# Focuser-proto.net
KiCad netlist of a schematic drawn in EAGLE
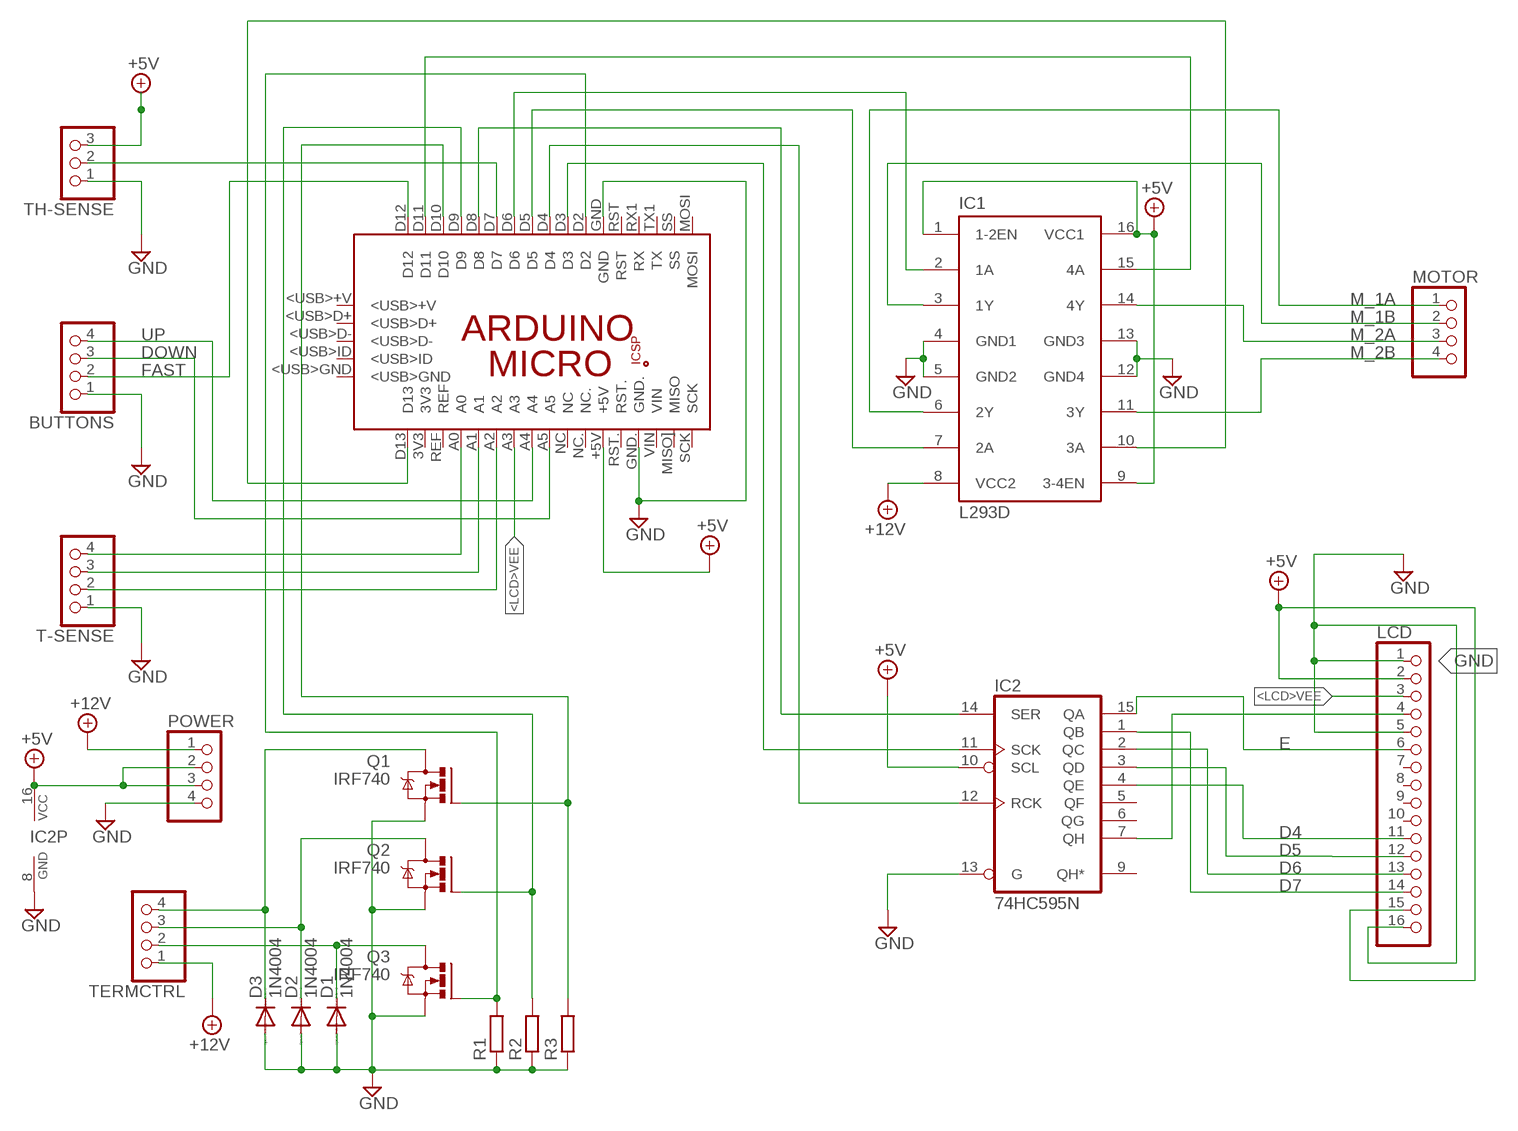
[diagram p0: schematic, sheet 1]

(export (version "E")
  (design (tool "Eeschema 10.0.6"))
  (components
    (comp (ref "BUTTONS")
      (value "PINHD-1X4")
      (footprint "eagle-import:1X04")
      (libsource (lib "eagle-import") (part "PINHD-1X4"))
    )
    (comp (ref "D1")
      (value "1N4004")
      (footprint "eagle-import:DO41-10")
      (libsource (lib "eagle-import") (part "1N4004"))
    )
    (comp (ref "D2")
      (value "1N4004")
      (footprint "eagle-import:DO41-10")
      (libsource (lib "eagle-import") (part "1N4004"))
    )
    (comp (ref "D3")
      (value "1N4004")
      (footprint "eagle-import:DO41-10")
      (libsource (lib "eagle-import") (part "1N4004"))
    )
    (comp (ref "IC1")
      (value "L293D")
      (footprint "eagle-import:DIL16")
      (libsource (lib "eagle-import") (part "L293D"))
    )
    (comp (ref "IC2")
      (value "74HC595N")
      (footprint "eagle-import:DIL16")
      (libsource (lib "eagle-import") (part "74595NHC"))
    )
    (comp (ref "LCD")
      (value "PINHD-1X16")
      (footprint "eagle-import:1X16")
      (libsource (lib "eagle-import") (part "PINHD-1X16"))
    )
    (comp (ref "MOTOR")
      (value "PINHD-1X4")
      (footprint "eagle-import:1X04")
      (libsource (lib "eagle-import") (part "PINHD-1X4"))
    )
    (comp (ref "PCB1")
      (value "ARDUINO_MICRO")
      (footprint "eagle-import:ARDUINO_MICRO")
      (libsource (lib "eagle-import") (part "ARDUINO_MICRO"))
    )
    (comp (ref "POWER")
      (value "PINHD-1X4")
      (footprint "eagle-import:1X04")
      (libsource (lib "eagle-import") (part "PINHD-1X4"))
    )
    (comp (ref "Q1")
      (value "IRF740")
      (footprint "eagle-import:TO220BV")
      (libsource (lib "eagle-import") (part "IRF740"))
    )
    (comp (ref "Q2")
      (value "IRF740")
      (footprint "eagle-import:TO220BV")
      (libsource (lib "eagle-import") (part "IRF740"))
    )
    (comp (ref "Q3")
      (value "IRF740")
      (footprint "eagle-import:TO220BV")
      (libsource (lib "eagle-import") (part "IRF740"))
    )
    (comp (ref "R1")
      (value "R-EU_0207/7")
      (footprint "eagle-import:0207_7")
      (libsource (lib "eagle-import") (part "R-EU_0207/7"))
    )
    (comp (ref "R2")
      (value "R-EU_0207/7")
      (footprint "eagle-import:0207_7")
      (libsource (lib "eagle-import") (part "R-EU_0207/7"))
    )
    (comp (ref "R3")
      (value "R-EU_0207/7")
      (footprint "eagle-import:0207_7")
      (libsource (lib "eagle-import") (part "R-EU_0207/7"))
    )
    (comp (ref "T-SENSE")
      (value "PINHD-1X4")
      (footprint "eagle-import:1X04")
      (libsource (lib "eagle-import") (part "PINHD-1X4"))
    )
    (comp (ref "TERMCTRL")
      (value "PINHD-1X4")
      (footprint "eagle-import:1X04")
      (libsource (lib "eagle-import") (part "PINHD-1X4"))
    )
    (comp (ref "TH-SENSE")
      (value "PINHD-1X3")
      (footprint "eagle-import:1X03")
      (libsource (lib "eagle-import") (part "PINHD-1X3"))
    )
  )
  (nets
    (net (code "1") (name "+5V") (class "Default")
      (node (ref "IC1") (pin "1") (pinfunction "1-2EN_1") (pintype "input"))
      (node (ref "IC1") (pin "16") (pinfunction "VCC1_16") (pintype "power_in"))
      (node (ref "IC1") (pin "9") (pinfunction "3-4EN_9") (pintype "input"))
      (node (ref "IC2") (pin "10") (pinfunction "SCL_10") (pintype "input"))
      (node (ref "IC2") (pin "16") (pinfunction "VCC_16") (pintype "power_in"))
      (node (ref "LCD") (pin "15") (pinfunction "15_15") (pintype "passive"))
      (node (ref "LCD") (pin "2") (pinfunction "2_2") (pintype "passive"))
      (node (ref "PCB1") (pin "+5V") (pinfunction "+5V_+5V") (pintype "bidirectional"))
      (node (ref "POWER") (pin "2") (pinfunction "2_2") (pintype "passive"))
      (node (ref "POWER") (pin "3") (pinfunction "3_3") (pintype "passive"))
      (node (ref "TH-SENSE") (pin "3") (pinfunction "3_3") (pintype "passive"))
    )
    (net (code "2") (name "+12V") (class "Default")
      (node (ref "IC1") (pin "8") (pinfunction "VCC2_8") (pintype "power_in"))
      (node (ref "POWER") (pin "1") (pinfunction "1_1") (pintype "passive"))
      (node (ref "TERMCTRL") (pin "1") (pinfunction "1_1") (pintype "passive"))
    )
    (net (code "3") (name "/D4") (class "Default")
      (node (ref "IC2") (pin "4") (pinfunction "QE_4") (pintype "tri_state"))
      (node (ref "LCD") (pin "11") (pinfunction "11_11") (pintype "passive"))
    )
    (net (code "4") (name "/D5") (class "Default")
      (node (ref "IC2") (pin "3") (pinfunction "QD_3") (pintype "tri_state"))
      (node (ref "LCD") (pin "12") (pinfunction "12_12") (pintype "passive"))
    )
    (net (code "5") (name "/D6") (class "Default")
      (node (ref "IC2") (pin "2") (pinfunction "QC_2") (pintype "tri_state"))
      (node (ref "LCD") (pin "13") (pinfunction "13_13") (pintype "passive"))
    )
    (net (code "6") (name "/D7") (class "Default")
      (node (ref "IC2") (pin "1") (pinfunction "QB_1") (pintype "tri_state"))
      (node (ref "LCD") (pin "14") (pinfunction "14_14") (pintype "passive"))
    )
    (net (code "7") (name "/DOWN") (class "Default")
      (node (ref "BUTTONS") (pin "3") (pinfunction "3_3") (pintype "passive"))
      (node (ref "PCB1") (pin "A5") (pinfunction "A5_A5") (pintype "bidirectional"))
    )
    (net (code "8") (name "/E") (class "Default")
      (node (ref "IC2") (pin "15") (pinfunction "QA_15") (pintype "tri_state"))
      (node (ref "LCD") (pin "6") (pinfunction "6_6") (pintype "passive"))
    )
    (net (code "9") (name "/FAST") (class "Default")
      (node (ref "BUTTONS") (pin "2") (pinfunction "2_2") (pintype "passive"))
      (node (ref "PCB1") (pin "D12") (pinfunction "D12_D12") (pintype "bidirectional"))
    )
    (net (code "10") (name "/M_1A") (class "Default")
      (node (ref "IC1") (pin "6") (pinfunction "2Y_6") (pintype "output"))
      (node (ref "MOTOR") (pin "1") (pinfunction "1_1") (pintype "passive"))
    )
    (net (code "11") (name "/M_1B") (class "Default")
      (node (ref "IC1") (pin "3") (pinfunction "1Y_3") (pintype "output"))
      (node (ref "MOTOR") (pin "2") (pinfunction "2_2") (pintype "passive"))
    )
    (net (code "12") (name "/M_2A") (class "Default")
      (node (ref "IC1") (pin "14") (pinfunction "4Y_14") (pintype "output"))
      (node (ref "MOTOR") (pin "3") (pinfunction "3_3") (pintype "passive"))
    )
    (net (code "13") (name "/M_2B") (class "Default")
      (node (ref "IC1") (pin "11") (pinfunction "3Y_11") (pintype "output"))
      (node (ref "MOTOR") (pin "4") (pinfunction "4_4") (pintype "passive"))
    )
    (net (code "14") (name "/UP") (class "Default")
      (node (ref "BUTTONS") (pin "4") (pinfunction "4_4") (pintype "passive"))
      (node (ref "PCB1") (pin "A4") (pinfunction "A4_A4") (pintype "bidirectional"))
    )
    (net (code "15") (name "<LCD>VEE") (class "Default")
      (node (ref "LCD") (pin "3") (pinfunction "3_3") (pintype "passive"))
      (node (ref "PCB1") (pin "A3") (pinfunction "A3_A3") (pintype "bidirectional"))
    )
    (net (code "16") (name "GND") (class "Default")
      (node (ref "BUTTONS") (pin "1") (pinfunction "1_1") (pintype "passive"))
      (node (ref "D1") (pin "A") (pinfunction "A_A") (pintype "passive"))
      (node (ref "D2") (pin "A") (pinfunction "A_A") (pintype "passive"))
      (node (ref "D3") (pin "A") (pinfunction "A_A") (pintype "passive"))
      (node (ref "IC1") (pin "12") (pinfunction "GND4_12") (pintype "power_in"))
      (node (ref "IC1") (pin "13") (pinfunction "GND3_13") (pintype "power_in"))
      (node (ref "IC1") (pin "4") (pinfunction "GND1_4") (pintype "power_in"))
      (node (ref "IC1") (pin "5") (pinfunction "GND2_5") (pintype "power_in"))
      (node (ref "IC2") (pin "13") (pinfunction "G_13") (pintype "input"))
      (node (ref "IC2") (pin "8") (pinfunction "GND_8") (pintype "power_in"))
      (node (ref "LCD") (pin "1") (pinfunction "1_1") (pintype "passive"))
      (node (ref "LCD") (pin "16") (pinfunction "16_16") (pintype "passive"))
      (node (ref "LCD") (pin "5") (pinfunction "5_5") (pintype "passive"))
      (node (ref "PCB1") (pin "GND") (pinfunction "GND_GND") (pintype "bidirectional"))
      (node (ref "PCB1") (pin "GND.") (pinfunction "GND._GND.") (pintype "bidirectional"))
      (node (ref "POWER") (pin "4") (pinfunction "4_4") (pintype "passive"))
      (node (ref "Q1") (pin "S") (pinfunction "S_S") (pintype "passive"))
      (node (ref "Q2") (pin "S") (pinfunction "S_S") (pintype "passive"))
      (node (ref "Q3") (pin "S") (pinfunction "S_S") (pintype "passive"))
      (node (ref "R1") (pin "1") (pinfunction "1_1") (pintype "passive"))
      (node (ref "R2") (pin "1") (pinfunction "1_1") (pintype "passive"))
      (node (ref "R3") (pin "1") (pinfunction "1_1") (pintype "passive"))
      (node (ref "T-SENSE") (pin "1") (pinfunction "1_1") (pintype "passive"))
      (node (ref "TH-SENSE") (pin "1") (pinfunction "1_1") (pintype "passive"))
    )
    (net (code "17") (name "Net-(D1-PadC)") (class "Default")
      (node (ref "D1") (pin "C") (pinfunction "C_C") (pintype "passive"))
      (node (ref "Q3") (pin "D") (pinfunction "D_D") (pintype "passive"))
      (node (ref "TERMCTRL") (pin "2") (pinfunction "2_2") (pintype "passive"))
    )
    (net (code "18") (name "Net-(D2-PadC)") (class "Default")
      (node (ref "D2") (pin "C") (pinfunction "C_C") (pintype "passive"))
      (node (ref "Q2") (pin "D") (pinfunction "D_D") (pintype "passive"))
      (node (ref "TERMCTRL") (pin "3") (pinfunction "3_3") (pintype "passive"))
    )
    (net (code "19") (name "Net-(D3-PadC)") (class "Default")
      (node (ref "D3") (pin "C") (pinfunction "C_C") (pintype "passive"))
      (node (ref "Q1") (pin "D") (pinfunction "D_D") (pintype "passive"))
      (node (ref "TERMCTRL") (pin "4") (pinfunction "4_4") (pintype "passive"))
    )
    (net (code "20") (name "Net-(IC1-1A)") (class "Default")
      (node (ref "IC1") (pin "2") (pinfunction "1A_2") (pintype "input"))
      (node (ref "PCB1") (pin "D6") (pinfunction "D6_D6") (pintype "bidirectional"))
    )
    (net (code "21") (name "Net-(IC1-2A)") (class "Default")
      (node (ref "IC1") (pin "7") (pinfunction "2A_7") (pintype "input"))
      (node (ref "PCB1") (pin "D5") (pinfunction "D5_D5") (pintype "bidirectional"))
    )
    (net (code "22") (name "Net-(IC1-3A)") (class "Default")
      (node (ref "IC1") (pin "10") (pinfunction "3A_10") (pintype "input"))
      (node (ref "PCB1") (pin "D13") (pinfunction "D13_D13") (pintype "bidirectional"))
    )
    (net (code "23") (name "Net-(IC1-4A)") (class "Default")
      (node (ref "IC1") (pin "15") (pinfunction "4A_15") (pintype "input"))
      (node (ref "PCB1") (pin "D11") (pinfunction "D11_D11") (pintype "bidirectional"))
    )
    (net (code "24") (name "Net-(IC2A-QH)") (class "Default")
      (node (ref "IC2") (pin "7") (pinfunction "QH_7") (pintype "tri_state"))
      (node (ref "LCD") (pin "4") (pinfunction "4_4") (pintype "passive"))
    )
    (net (code "25") (name "Net-(IC2A-RCK)") (class "Default")
      (node (ref "IC2") (pin "12") (pinfunction "RCK_12") (pintype "input"))
      (node (ref "PCB1") (pin "D4") (pinfunction "D4_D4") (pintype "bidirectional"))
    )
    (net (code "26") (name "Net-(IC2A-SCK)") (class "Default")
      (node (ref "IC2") (pin "11") (pinfunction "SCK_11") (pintype "input"))
      (node (ref "PCB1") (pin "D3") (pinfunction "D3_D3") (pintype "bidirectional"))
    )
    (net (code "27") (name "Net-(IC2A-SER)") (class "Default")
      (node (ref "IC2") (pin "14") (pinfunction "SER_14") (pintype "input"))
      (node (ref "PCB1") (pin "D8") (pinfunction "D8_D8") (pintype "bidirectional"))
    )
    (net (code "28") (name "Net-(PCB1-PadA0)") (class "Default")
      (node (ref "PCB1") (pin "A0") (pinfunction "A0_A0") (pintype "bidirectional"))
      (node (ref "T-SENSE") (pin "4") (pinfunction "4_4") (pintype "passive"))
    )
    (net (code "29") (name "Net-(PCB1-PadA1)") (class "Default")
      (node (ref "PCB1") (pin "A1") (pinfunction "A1_A1") (pintype "bidirectional"))
      (node (ref "T-SENSE") (pin "3") (pinfunction "3_3") (pintype "passive"))
    )
    (net (code "30") (name "Net-(PCB1-PadA2)") (class "Default")
      (node (ref "PCB1") (pin "A2") (pinfunction "A2_A2") (pintype "bidirectional"))
      (node (ref "T-SENSE") (pin "2") (pinfunction "2_2") (pintype "passive"))
    )
    (net (code "31") (name "Net-(PCB1-PadD2)") (class "Default")
      (node (ref "PCB1") (pin "D2") (pinfunction "D2_D2") (pintype "bidirectional"))
      (node (ref "Q3") (pin "G") (pinfunction "G_G") (pintype "passive"))
      (node (ref "R1") (pin "2") (pinfunction "2_2") (pintype "passive"))
    )
    (net (code "32") (name "Net-(PCB1-PadD7)") (class "Default")
      (node (ref "PCB1") (pin "D7") (pinfunction "D7_D7") (pintype "bidirectional"))
      (node (ref "TH-SENSE") (pin "2") (pinfunction "2_2") (pintype "passive"))
    )
    (net (code "33") (name "Net-(PCB1-PadD9)") (class "Default")
      (node (ref "PCB1") (pin "D9") (pinfunction "D9_D9") (pintype "bidirectional"))
      (node (ref "Q2") (pin "G") (pinfunction "G_G") (pintype "passive"))
      (node (ref "R2") (pin "2") (pinfunction "2_2") (pintype "passive"))
    )
    (net (code "34") (name "Net-(PCB1-PadD10)") (class "Default")
      (node (ref "PCB1") (pin "D10") (pinfunction "D10_D10") (pintype "bidirectional"))
      (node (ref "Q1") (pin "G") (pinfunction "G_G") (pintype "passive"))
      (node (ref "R3") (pin "2") (pinfunction "2_2") (pintype "passive"))
    )
    (net (code "35") (name "unconnected-(IC2A-QF-Pad5)") (class "Default")
      (node (ref "IC2") (pin "5") (pinfunction "QF_5") (pintype "tri_state"))
    )
    (net (code "36") (name "unconnected-(IC2A-QG-Pad6)") (class "Default")
      (node (ref "IC2") (pin "6") (pinfunction "QG_6") (pintype "tri_state"))
    )
    (net (code "37") (name "unconnected-(IC2A-QH*-Pad9)") (class "Default")
      (node (ref "IC2") (pin "9") (pinfunction "QH*_9") (pintype "tri_state"))
    )
    (net (code "38") (name "unconnected-(LCD-Pad7)") (class "Default")
      (node (ref "LCD") (pin "7") (pinfunction "7_7") (pintype "passive"))
    )
    (net (code "39") (name "unconnected-(LCD-Pad8)") (class "Default")
      (node (ref "LCD") (pin "8") (pinfunction "8_8") (pintype "passive"))
    )
    (net (code "40") (name "unconnected-(LCD-Pad9)") (class "Default")
      (node (ref "LCD") (pin "9") (pinfunction "9_9") (pintype "passive"))
    )
    (net (code "41") (name "unconnected-(LCD-Pad10)") (class "Default")
      (node (ref "LCD") (pin "10") (pinfunction "10_10") (pintype "passive"))
    )
    (net (code "42") (name "unconnected-(PCB1-MISO-PadMISO])") (class "Default")
      (node (ref "PCB1") (pin "MISO]") (pinfunction "MISO_MISO]") (pintype "bidirectional"))
    )
    (net (code "43") (name "unconnected-(PCB1-Pad3V3)") (class "Default")
      (node (ref "PCB1") (pin "3V3") (pinfunction "3V3_3V3") (pintype "bidirectional"))
    )
    (net (code "44") (name "unconnected-(PCB1-Pad5V)") (class "Default")
      (node (ref "PCB1") (pin "5V") (pinfunction "5V_5V") (pintype "bidirectional"))
    )
    (net (code "45") (name "unconnected-(PCB1-Pad<USB>+V)") (class "Default")
      (node (ref "PCB1") (pin "<USB>+V") (pinfunction "<USB>+V_<USB>+V") (pintype "bidirectional"))
    )
    (net (code "46") (name "unconnected-(PCB1-Pad<USB>D+)") (class "Default")
      (node (ref "PCB1") (pin "<USB>D+") (pinfunction "<USB>D+_<USB>D+") (pintype "bidirectional"))
    )
    (net (code "47") (name "unconnected-(PCB1-Pad<USB>D-)") (class "Default")
      (node (ref "PCB1") (pin "<USB>D-") (pinfunction "<USB>D-_<USB>D-") (pintype "bidirectional"))
    )
    (net (code "48") (name "unconnected-(PCB1-Pad<USB>GND)") (class "Default")
      (node (ref "PCB1") (pin "<USB>GND") (pinfunction "<USB>GND_<USB>GND") (pintype "bidirectional"))
    )
    (net (code "49") (name "unconnected-(PCB1-Pad<USB>ID)") (class "Default")
      (node (ref "PCB1") (pin "<USB>ID") (pinfunction "<USB>ID_<USB>ID") (pintype "bidirectional"))
    )
    (net (code "50") (name "unconnected-(PCB1-PadGND_)") (class "Default")
      (node (ref "PCB1") (pin "GND_") (pinfunction "GND__GND_") (pintype "bidirectional"))
    )
    (net (code "51") (name "unconnected-(PCB1-PadMISO.)") (class "Default")
      (node (ref "PCB1") (pin "MISO.") (pinfunction "MISO._MISO.") (pintype "bidirectional"))
    )
    (net (code "52") (name "unconnected-(PCB1-PadMOSI)") (class "Default")
      (node (ref "PCB1") (pin "MOSI") (pinfunction "MOSI_MOSI") (pintype "bidirectional"))
    )
    (net (code "53") (name "unconnected-(PCB1-PadMOSI.)") (class "Default")
      (node (ref "PCB1") (pin "MOSI.") (pinfunction "MOSI._MOSI.") (pintype "bidirectional"))
    )
    (net (code "54") (name "unconnected-(PCB1-PadNC)") (class "Default")
      (node (ref "PCB1") (pin "NC") (pinfunction "NC_NC") (pintype "bidirectional"))
    )
    (net (code "55") (name "unconnected-(PCB1-PadNC.)") (class "Default")
      (node (ref "PCB1") (pin "NC.") (pinfunction "NC._NC.") (pintype "bidirectional"))
    )
    (net (code "56") (name "unconnected-(PCB1-PadREF)") (class "Default")
      (node (ref "PCB1") (pin "REF") (pinfunction "REF_REF") (pintype "bidirectional"))
    )
    (net (code "57") (name "unconnected-(PCB1-PadRESET..)") (class "Default")
      (node (ref "PCB1") (pin "RESET..") (pinfunction "RESET.._RESET..") (pintype "bidirectional"))
    )
    (net (code "58") (name "unconnected-(PCB1-PadRST)") (class "Default")
      (node (ref "PCB1") (pin "RST") (pinfunction "RST_RST") (pintype "bidirectional"))
    )
    (net (code "59") (name "unconnected-(PCB1-PadRST.)") (class "Default")
      (node (ref "PCB1") (pin "RST.") (pinfunction "RST._RST.") (pintype "bidirectional"))
    )
    (net (code "60") (name "unconnected-(PCB1-PadSCK)") (class "Default")
      (node (ref "PCB1") (pin "SCK") (pinfunction "SCK_SCK") (pintype "bidirectional"))
    )
    (net (code "61") (name "unconnected-(PCB1-PadSCK.)") (class "Default")
      (node (ref "PCB1") (pin "SCK.") (pinfunction "SCK._SCK.") (pintype "bidirectional"))
    )
    (net (code "62") (name "unconnected-(PCB1-PadSS)") (class "Default")
      (node (ref "PCB1") (pin "SS") (pinfunction "SS_SS") (pintype "bidirectional"))
    )
    (net (code "63") (name "unconnected-(PCB1-PadVIN)") (class "Default")
      (node (ref "PCB1") (pin "VIN") (pinfunction "VIN_VIN") (pintype "bidirectional"))
    )
    (net (code "64") (name "unconnected-(PCB1-RX-PadRX1)") (class "Default")
      (node (ref "PCB1") (pin "RX1") (pinfunction "RX_RX1") (pintype "bidirectional"))
    )
    (net (code "65") (name "unconnected-(PCB1-TX-PadTX1)") (class "Default")
      (node (ref "PCB1") (pin "TX1") (pinfunction "TX_TX1") (pintype "bidirectional"))
    )
  )
)
